# Nintendo_2DS_USB-C.net
KiCad netlist of a schematic drawn in EAGLE
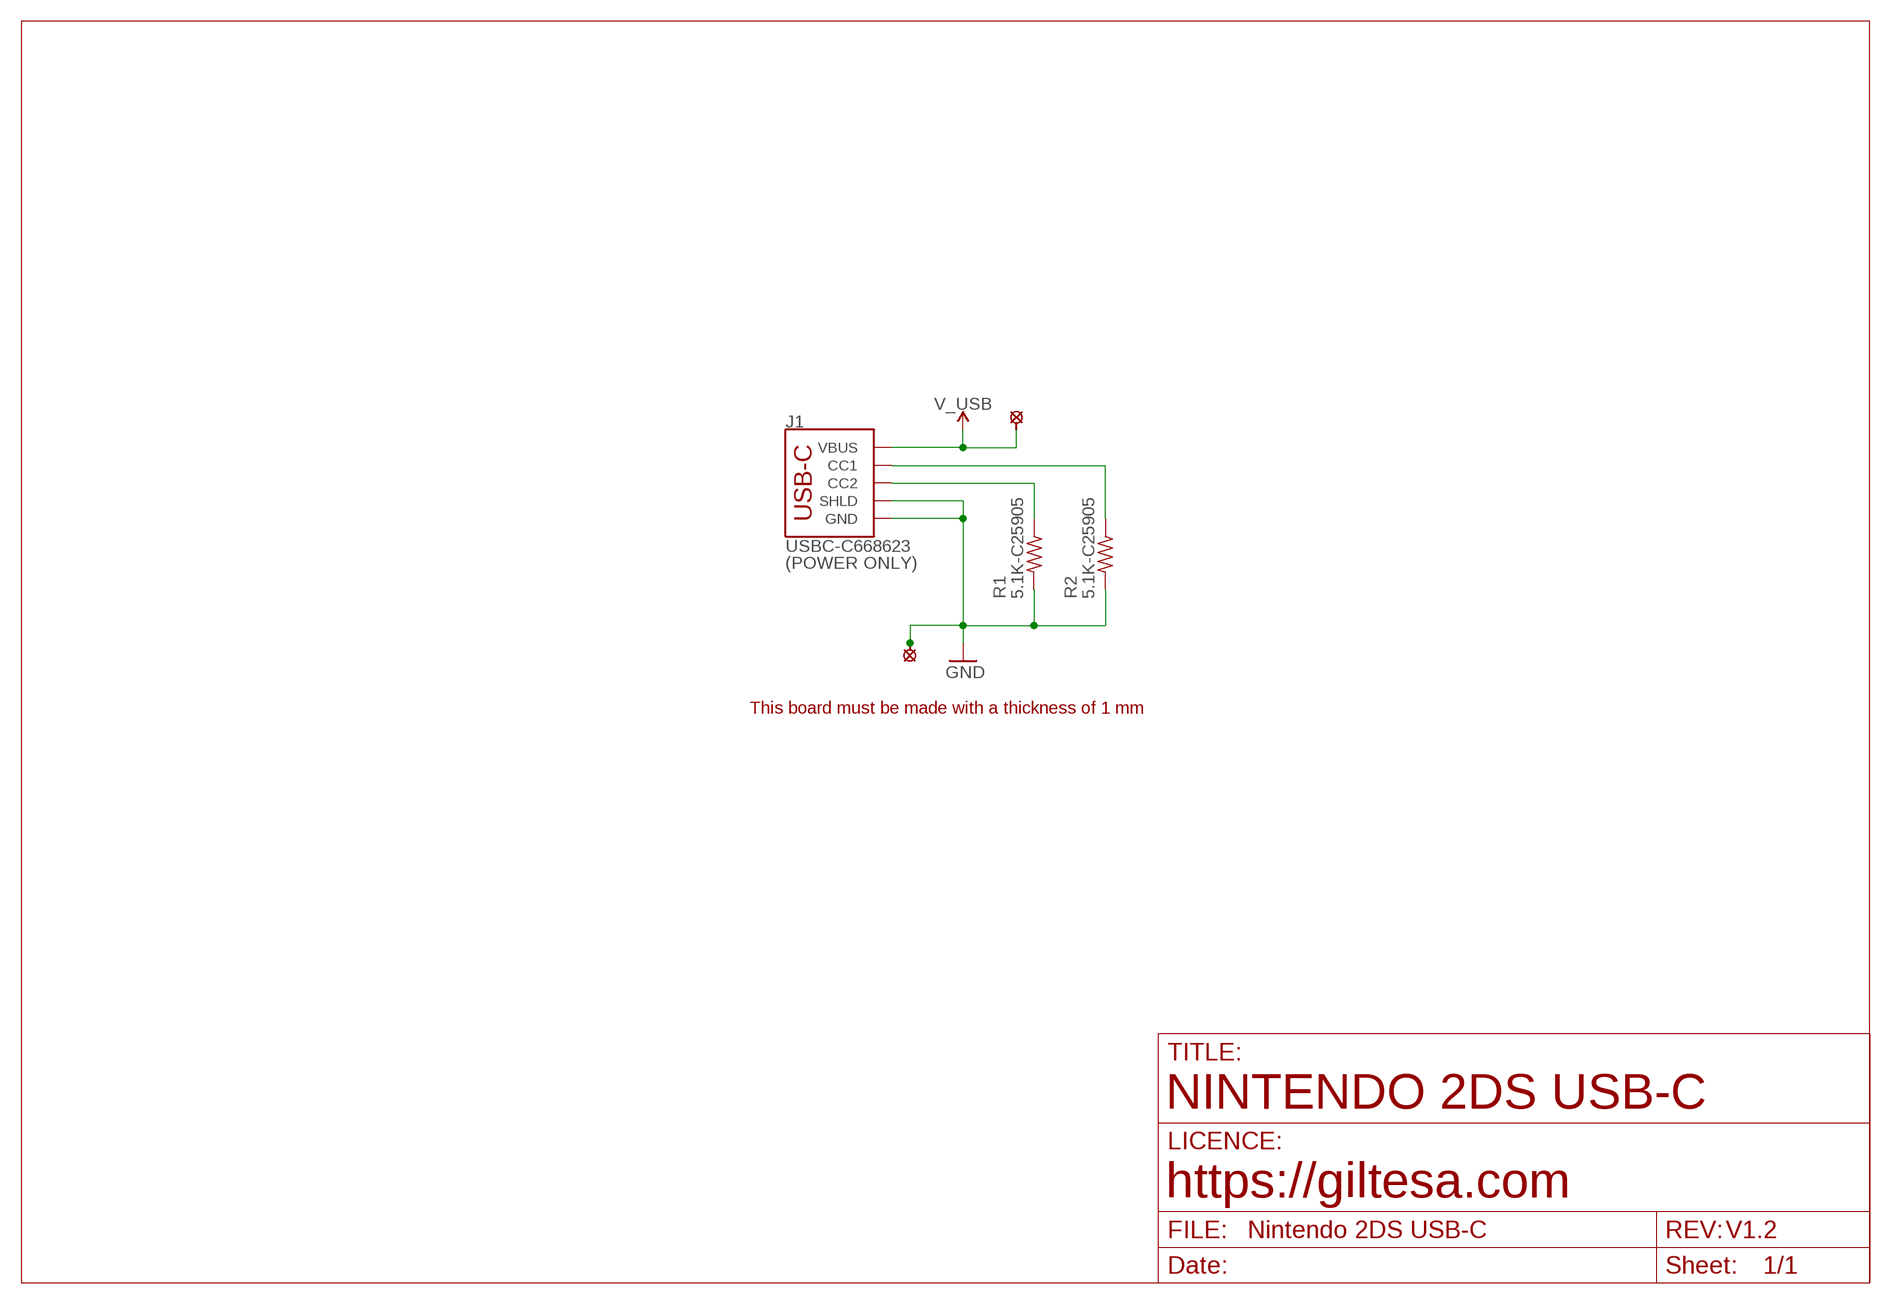
[diagram p0: schematic, sheet 1]

(export (version "E")
  (design (tool "Eeschema 10.0.6"))
  (components
    (comp (ref "J1")
      (value "USBC-C668623")
      (footprint "eagle-import:USB-C_6P")
      (libsource (lib "eagle-import") (part "USB-C_6P_POWER"))
    )
    (comp (ref "R1")
      (value "5.1K-C25905")
      (footprint "eagle-import:R0402")
      (libsource (lib "eagle-import") (part "R0402"))
    )
    (comp (ref "R2")
      (value "5.1K-C25905")
      (footprint "eagle-import:R0402")
      (libsource (lib "eagle-import") (part "R0402"))
    )
    (comp (ref "U$2")
      (value "PAD_1.0H")
      (footprint "eagle-import:PAD_1.0_HALF_MASK")
      (libsource (lib "eagle-import") (part "PAD_1.0H"))
    )
    (comp (ref "U$3")
      (value "PAD_1.0H")
      (footprint "eagle-import:PAD_1.0_HALF_MASK")
      (libsource (lib "eagle-import") (part "PAD_1.0H"))
    )
    (comp (ref "U$4")
      (value "PAD_1.0H")
      (footprint "eagle-import:PAD_1.0_HALF_MASK")
      (libsource (lib "eagle-import") (part "PAD_1.0H"))
    )
    (comp (ref "U$5")
      (value "PAD_1.0H")
      (footprint "eagle-import:PAD_1.0_HALF_MASK")
      (libsource (lib "eagle-import") (part "PAD_1.0H"))
    )
  )
  (nets
    (net (code "1") (name "GND") (class "Default")
      (node (ref "J1") (pin "A12-GND") (pinfunction "GND_A12-GND") (pintype "bidirectional"))
      (node (ref "J1") (pin "B12-GND") (pinfunction "GND_B12-GND") (pintype "bidirectional"))
      (node (ref "J1") (pin "SHLD1") (pinfunction "SHLD_SHLD1") (pintype "bidirectional"))
      (node (ref "J1") (pin "SHLD2") (pinfunction "SHLD_SHLD2") (pintype "bidirectional"))
      (node (ref "J1") (pin "SHLD3") (pinfunction "SHLD_SHLD3") (pintype "bidirectional"))
      (node (ref "J1") (pin "SHLD4") (pinfunction "SHLD_SHLD4") (pintype "bidirectional"))
      (node (ref "R1") (pin "2") (pinfunction "2_2") (pintype "passive"))
      (node (ref "R2") (pin "2") (pinfunction "2_2") (pintype "passive"))
      (node (ref "U$3") (pin "P$1") (pinfunction "P$1_P$1") (pintype "bidirectional"))
      (node (ref "U$4") (pin "P$1") (pinfunction "P$1_P$1") (pintype "bidirectional"))
      (node (ref "U$5") (pin "P$1") (pinfunction "P$1_P$1") (pintype "bidirectional"))
    )
    (net (code "2") (name "Net-(J1-CC1)") (class "Default")
      (node (ref "J1") (pin "A5") (pinfunction "CC1_A5") (pintype "bidirectional"))
      (node (ref "R2") (pin "1") (pinfunction "1_1") (pintype "passive"))
    )
    (net (code "3") (name "Net-(J1-CC2)") (class "Default")
      (node (ref "J1") (pin "B5") (pinfunction "CC2_B5") (pintype "bidirectional"))
      (node (ref "R1") (pin "1") (pinfunction "1_1") (pintype "passive"))
    )
    (net (code "4") (name "V_USB") (class "Default")
      (node (ref "J1") (pin "A9-VBUS") (pinfunction "VBUS_A9-VBUS") (pintype "bidirectional"))
      (node (ref "J1") (pin "B9-VBUS") (pinfunction "VBUS_B9-VBUS") (pintype "bidirectional"))
      (node (ref "U$2") (pin "P$1") (pinfunction "P$1_P$1") (pintype "bidirectional"))
    )
  )
)
